# Full_power.net
KiCad netlist of a schematic drawn in EAGLE
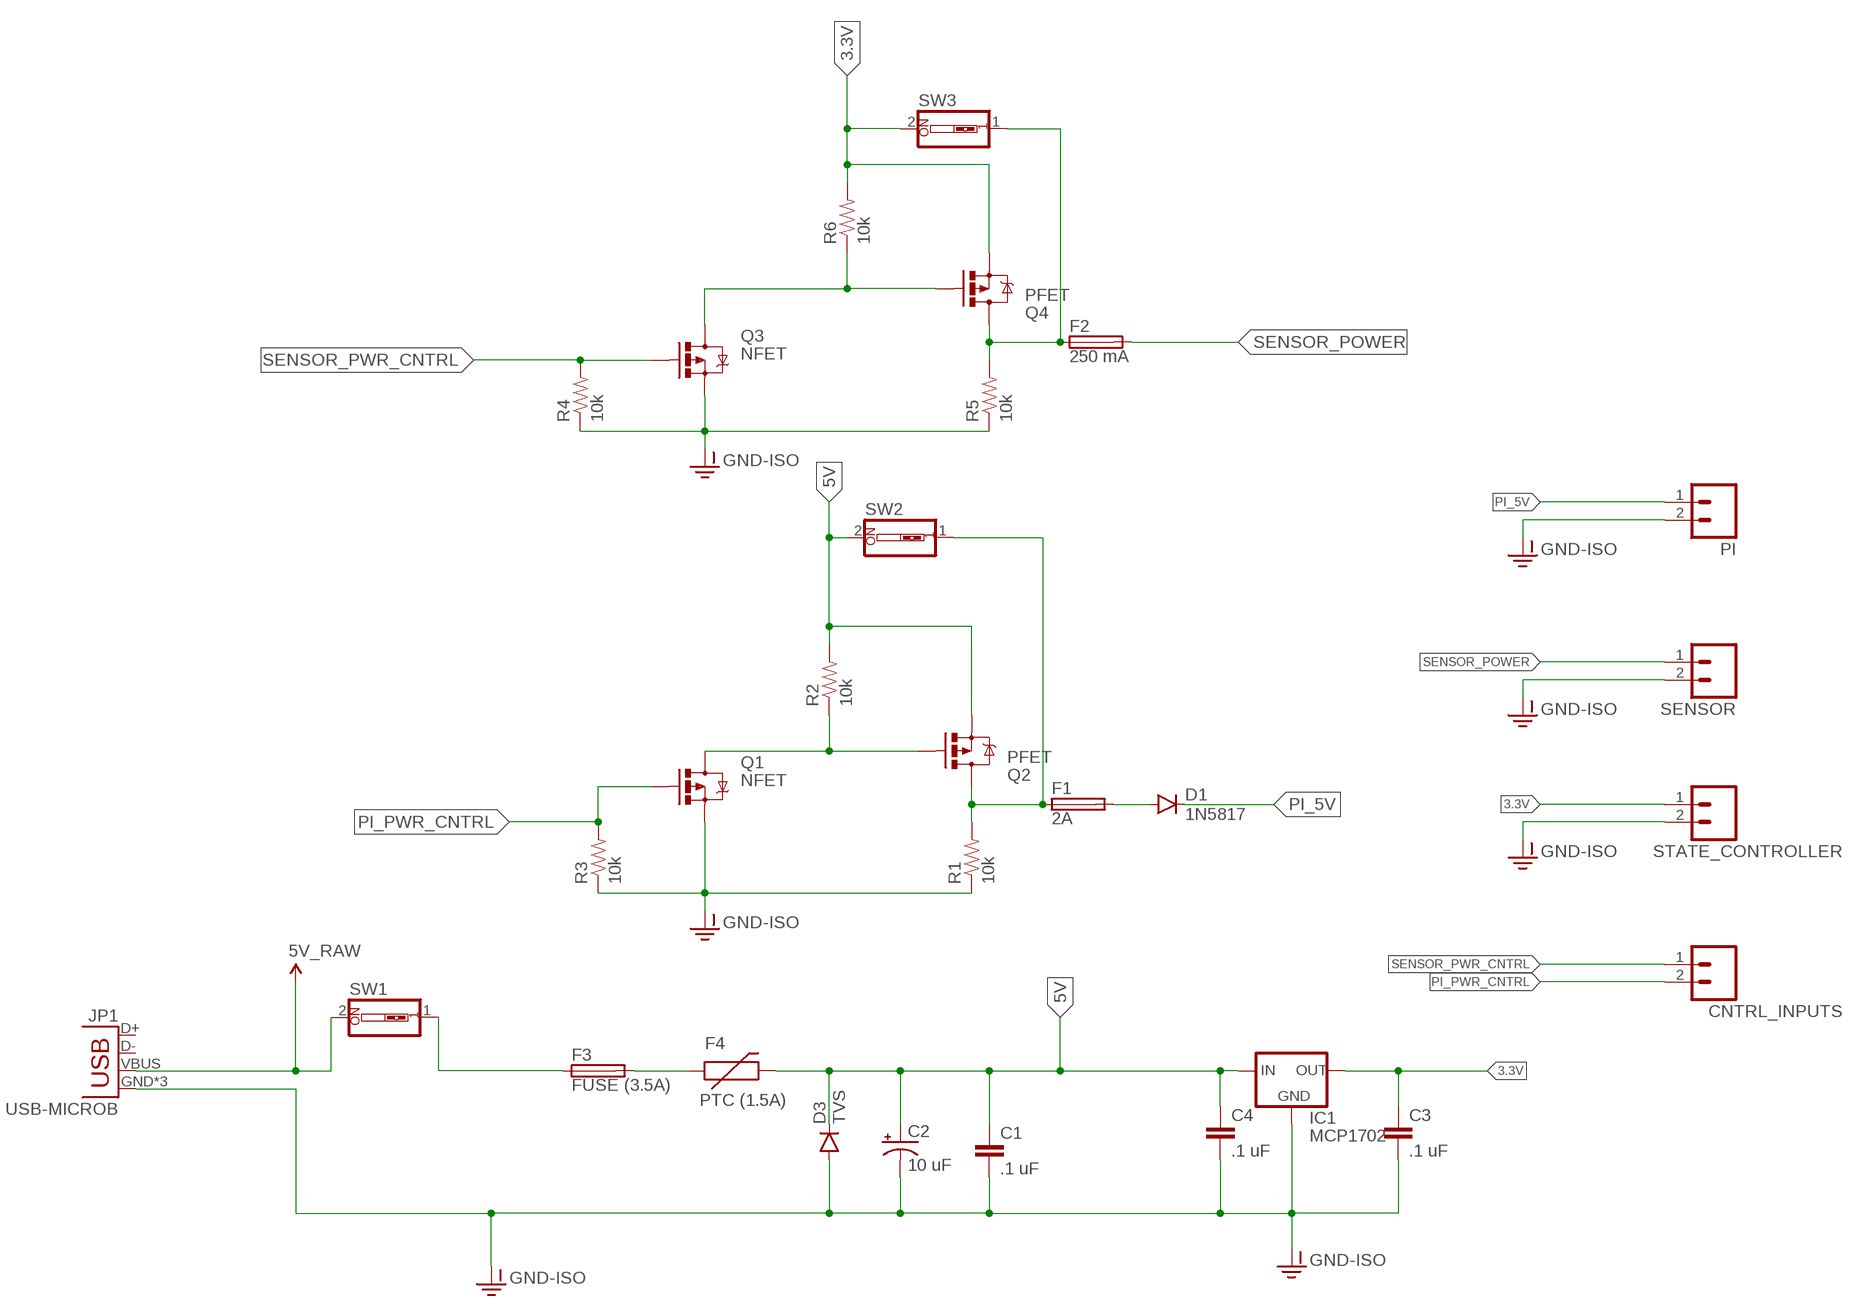
[diagram p0: schematic, sheet 1]

(export (version "E")
  (design (tool "Eeschema 10.0.6"))
  (components
    (comp (ref "C1")
      (value ".1 uF")
      (footprint "eagle-import:CAP-PTH-SMALL")
      (libsource (lib "eagle-import") (part "SparkFun-Passives_CAPPTH"))
    )
    (comp (ref "C2")
      (value "10 uF")
      (footprint "eagle-import:CPOL-RADIAL-10UF-25V")
      (libsource (lib "eagle-import") (part "CAP_POLPTH2"))
    )
    (comp (ref "C3")
      (value ".1 uF")
      (footprint "eagle-import:CAP-PTH-SMALL")
      (libsource (lib "eagle-import") (part "CAPPTH"))
    )
    (comp (ref "C4")
      (value ".1 uF")
      (footprint "eagle-import:CAP-PTH-SMALL")
      (libsource (lib "eagle-import") (part "CAPPTH"))
    )
    (comp (ref "CNTRL_INPUTS")
      (value "M02PTH")
      (footprint "eagle-import:1X02")
      (libsource (lib "eagle-import") (part "M02PTH"))
    )
    (comp (ref "D1")
      (value "1N5817")
      (footprint "eagle-import:DIODE-1N4001")
      (libsource (lib "eagle-import") (part "DIODEPTH"))
    )
    (comp (ref "D3")
      (value "TVS")
      (footprint "eagle-import:DIODE-1N4001")
      (libsource (lib "eagle-import") (part "DIODEPTH"))
    )
    (comp (ref "F1")
      (value "2A")
      (footprint "eagle-import:PICOFUSE")
      (libsource (lib "eagle-import") (part "FUSEPICOFUSE"))
    )
    (comp (ref "F2")
      (value "250 mA")
      (footprint "eagle-import:PICOFUSE")
      (libsource (lib "eagle-import") (part "FUSEPICOFUSE"))
    )
    (comp (ref "F3")
      (value "FUSE (3.5A)")
      (footprint "eagle-import:PICOFUSE")
      (libsource (lib "eagle-import") (part "PICOFUSE"))
    )
    (comp (ref "F4")
      (value "PTC (1.5A)")
      (footprint "eagle-import:PTC")
      (libsource (lib "eagle-import") (part "PTCPTH"))
    )
    (comp (ref "IC1")
      (value "MCP1702")
      (footprint "eagle-import:TO92")
      (libsource (lib "eagle-import") (part "MCP1700TRI"))
    )
    (comp (ref "JP1")
      (value "USB-MICROB")
      (footprint "eagle-import:USB-MICROB")
      (libsource (lib "eagle-import") (part "USB-MICROB"))
    )
    (comp (ref "PI")
      (value "M02PTH")
      (footprint "eagle-import:1X02")
      (libsource (lib "eagle-import") (part "M02PTH"))
    )
    (comp (ref "Q1")
      (value "NFET")
      (footprint "eagle-import:TO220V")
      (libsource (lib "eagle-import") (part "MOSFET-PCHANNELFQP27P06"))
    )
    (comp (ref "Q2")
      (value "PFET")
      (footprint "eagle-import:TO220V")
      (libsource (lib "eagle-import") (part "MOSFET-PCHANNELFQP27P06"))
    )
    (comp (ref "Q3")
      (value "NFET")
      (footprint "eagle-import:TO220V")
      (libsource (lib "eagle-import") (part "MOSFET-PCHANNELFQP27P06"))
    )
    (comp (ref "Q4")
      (value "PFET")
      (footprint "eagle-import:TO220V")
      (libsource (lib "eagle-import") (part "MOSFET-PCHANNELFQP27P06"))
    )
    (comp (ref "R1")
      (value "10k")
      (footprint "eagle-import:1206")
      (libsource (lib "eagle-import") (part "RESISTOR1206"))
    )
    (comp (ref "R2")
      (value "10k")
      (footprint "eagle-import:1206")
      (libsource (lib "eagle-import") (part "RESISTOR1206"))
    )
    (comp (ref "R3")
      (value "10k")
      (footprint "eagle-import:1206")
      (libsource (lib "eagle-import") (part "RESISTOR1206"))
    )
    (comp (ref "R4")
      (value "10k")
      (footprint "eagle-import:1206")
      (libsource (lib "eagle-import") (part "RESISTOR1206"))
    )
    (comp (ref "R5")
      (value "10k")
      (footprint "eagle-import:1206")
      (libsource (lib "eagle-import") (part "RESISTOR1206"))
    )
    (comp (ref "R6")
      (value "10k")
      (footprint "eagle-import:1206")
      (libsource (lib "eagle-import") (part "RESISTOR1206"))
    )
    (comp (ref "SENSOR")
      (value "M02PTH")
      (footprint "eagle-import:1X02")
      (libsource (lib "eagle-import") (part "M02PTH"))
    )
    (comp (ref "STATE_CONTROLLER")
      (value "M02PTH")
      (footprint "eagle-import:1X02")
      (libsource (lib "eagle-import") (part "M02PTH"))
    )
    (comp (ref "SW1")
      (value "SW_DIP-1")
      (footprint "eagle-import:EDG-01")
      (libsource (lib "eagle-import") (part "SW_DIP-1"))
    )
    (comp (ref "SW2")
      (value "SW_DIP-1")
      (footprint "eagle-import:EDG-01")
      (libsource (lib "eagle-import") (part "SW_DIP-1"))
    )
    (comp (ref "SW3")
      (value "SW_DIP-1")
      (footprint "eagle-import:EDG-01")
      (libsource (lib "eagle-import") (part "SW_DIP-1"))
    )
  )
  (nets
    (net (code "1") (name "3.3V") (class "Default")
      (node (ref "C3") (pin "1") (pinfunction "1_1") (pintype "passive"))
      (node (ref "IC1") (pin "3") (pinfunction "OUT_3") (pintype "passive"))
      (node (ref "Q4") (pin "3") (pinfunction "S_3") (pintype "passive"))
      (node (ref "R6") (pin "2") (pinfunction "2_2") (pintype "passive"))
      (node (ref "STATE_CONTROLLER") (pin "1") (pinfunction "1_1") (pintype "passive"))
      (node (ref "SW3") (pin "2") (pinfunction "2_2") (pintype "passive"))
    )
    (net (code "2") (name "5V") (class "Default")
      (node (ref "C1") (pin "1") (pinfunction "1_1") (pintype "passive"))
      (node (ref "C2") (pin "1") (pinfunction "+_1") (pintype "passive"))
      (node (ref "C4") (pin "1") (pinfunction "1_1") (pintype "passive"))
      (node (ref "D3") (pin "C") (pinfunction "C_C") (pintype "passive"))
      (node (ref "F4") (pin "P$2") (pinfunction "2_P$2") (pintype "bidirectional"))
      (node (ref "IC1") (pin "2") (pinfunction "IN_2") (pintype "input"))
      (node (ref "Q2") (pin "3") (pinfunction "S_3") (pintype "passive"))
      (node (ref "R2") (pin "2") (pinfunction "2_2") (pintype "passive"))
      (node (ref "SW2") (pin "2") (pinfunction "2_2") (pintype "passive"))
    )
    (net (code "3") (name "5V_RAW") (class "Default")
      (node (ref "JP1") (pin "VBUS") (pinfunction "VBUS_VBUS") (pintype "bidirectional"))
      (node (ref "SW1") (pin "2") (pinfunction "2_2") (pintype "passive"))
    )
    (net (code "4") (name "GND-ISO") (class "Default")
      (node (ref "C1") (pin "2") (pinfunction "2_2") (pintype "passive"))
      (node (ref "C2") (pin "2") (pinfunction "-_2") (pintype "passive"))
      (node (ref "C3") (pin "2") (pinfunction "2_2") (pintype "passive"))
      (node (ref "C4") (pin "2") (pinfunction "2_2") (pintype "passive"))
      (node (ref "D3") (pin "A") (pinfunction "A_A") (pintype "passive"))
      (node (ref "IC1") (pin "1") (pinfunction "GND_1") (pintype "input"))
      (node (ref "JP1") (pin "GND") (pinfunction "GND_GND") (pintype "bidirectional"))
      (node (ref "JP1") (pin "MT1") (pinfunction "GND_MT1") (pintype "bidirectional"))
      (node (ref "JP1") (pin "MT2") (pinfunction "GND_MT2") (pintype "bidirectional"))
      (node (ref "PI") (pin "2") (pinfunction "2_2") (pintype "passive"))
      (node (ref "Q1") (pin "3") (pinfunction "S_3") (pintype "passive"))
      (node (ref "Q3") (pin "3") (pinfunction "S_3") (pintype "passive"))
      (node (ref "R1") (pin "1") (pinfunction "1_1") (pintype "passive"))
      (node (ref "R3") (pin "1") (pinfunction "1_1") (pintype "passive"))
      (node (ref "R4") (pin "1") (pinfunction "1_1") (pintype "passive"))
      (node (ref "R5") (pin "1") (pinfunction "1_1") (pintype "passive"))
      (node (ref "SENSOR") (pin "2") (pinfunction "2_2") (pintype "passive"))
      (node (ref "STATE_CONTROLLER") (pin "2") (pinfunction "2_2") (pintype "passive"))
    )
    (net (code "5") (name "Net-(D1-PadA)") (class "Default")
      (node (ref "D1") (pin "A") (pinfunction "A_A") (pintype "passive"))
      (node (ref "F1") (pin "2") (pinfunction "2_2") (pintype "passive"))
    )
    (net (code "6") (name "Net-(F3-Pad1)") (class "Default")
      (node (ref "F3") (pin "1") (pinfunction "1_1") (pintype "passive"))
      (node (ref "SW1") (pin "1") (pinfunction "1_1") (pintype "passive"))
    )
    (net (code "7") (name "Net-(F4-1)") (class "Default")
      (node (ref "F3") (pin "2") (pinfunction "2_2") (pintype "passive"))
      (node (ref "F4") (pin "P$1") (pinfunction "1_P$1") (pintype "bidirectional"))
    )
    (net (code "8") (name "Net-(Q1-D)") (class "Default")
      (node (ref "Q1") (pin "2") (pinfunction "D_2") (pintype "passive"))
      (node (ref "Q2") (pin "1") (pinfunction "G_1") (pintype "passive"))
      (node (ref "R2") (pin "1") (pinfunction "1_1") (pintype "passive"))
    )
    (net (code "9") (name "Net-(Q2-D)") (class "Default")
      (node (ref "F1") (pin "1") (pinfunction "1_1") (pintype "passive"))
      (node (ref "Q2") (pin "2") (pinfunction "D_2") (pintype "passive"))
      (node (ref "R1") (pin "2") (pinfunction "2_2") (pintype "passive"))
      (node (ref "SW2") (pin "1") (pinfunction "1_1") (pintype "passive"))
    )
    (net (code "10") (name "Net-(Q3-D)") (class "Default")
      (node (ref "Q3") (pin "2") (pinfunction "D_2") (pintype "passive"))
      (node (ref "Q4") (pin "1") (pinfunction "G_1") (pintype "passive"))
      (node (ref "R6") (pin "1") (pinfunction "1_1") (pintype "passive"))
    )
    (net (code "11") (name "Net-(Q4-D)") (class "Default")
      (node (ref "F2") (pin "1") (pinfunction "1_1") (pintype "passive"))
      (node (ref "Q4") (pin "2") (pinfunction "D_2") (pintype "passive"))
      (node (ref "R5") (pin "2") (pinfunction "2_2") (pintype "passive"))
      (node (ref "SW3") (pin "1") (pinfunction "1_1") (pintype "passive"))
    )
    (net (code "12") (name "PI_5V") (class "Default")
      (node (ref "D1") (pin "C") (pinfunction "C_C") (pintype "passive"))
      (node (ref "PI") (pin "1") (pinfunction "1_1") (pintype "passive"))
    )
    (net (code "13") (name "PI_PWR_CNTRL") (class "Default")
      (node (ref "CNTRL_INPUTS") (pin "2") (pinfunction "2_2") (pintype "passive"))
      (node (ref "Q1") (pin "1") (pinfunction "G_1") (pintype "passive"))
      (node (ref "R3") (pin "2") (pinfunction "2_2") (pintype "passive"))
    )
    (net (code "14") (name "SENSOR_POWER") (class "Default")
      (node (ref "F2") (pin "2") (pinfunction "2_2") (pintype "passive"))
      (node (ref "SENSOR") (pin "1") (pinfunction "1_1") (pintype "passive"))
    )
    (net (code "15") (name "SENSOR_PWR_CNTRL") (class "Default")
      (node (ref "CNTRL_INPUTS") (pin "1") (pinfunction "1_1") (pintype "passive"))
      (node (ref "Q3") (pin "1") (pinfunction "G_1") (pintype "passive"))
      (node (ref "R4") (pin "2") (pinfunction "2_2") (pintype "passive"))
    )
    (net (code "16") (name "unconnected-(JP1-PadD+)") (class "Default")
      (node (ref "JP1") (pin "D+") (pinfunction "D+_D+") (pintype "bidirectional"))
    )
    (net (code "17") (name "unconnected-(JP1-PadD-)") (class "Default")
      (node (ref "JP1") (pin "D-") (pinfunction "D-_D-") (pintype "bidirectional"))
    )
  )
)
